# PLC.net
KiCad netlist of a schematic drawn in Altium Designer
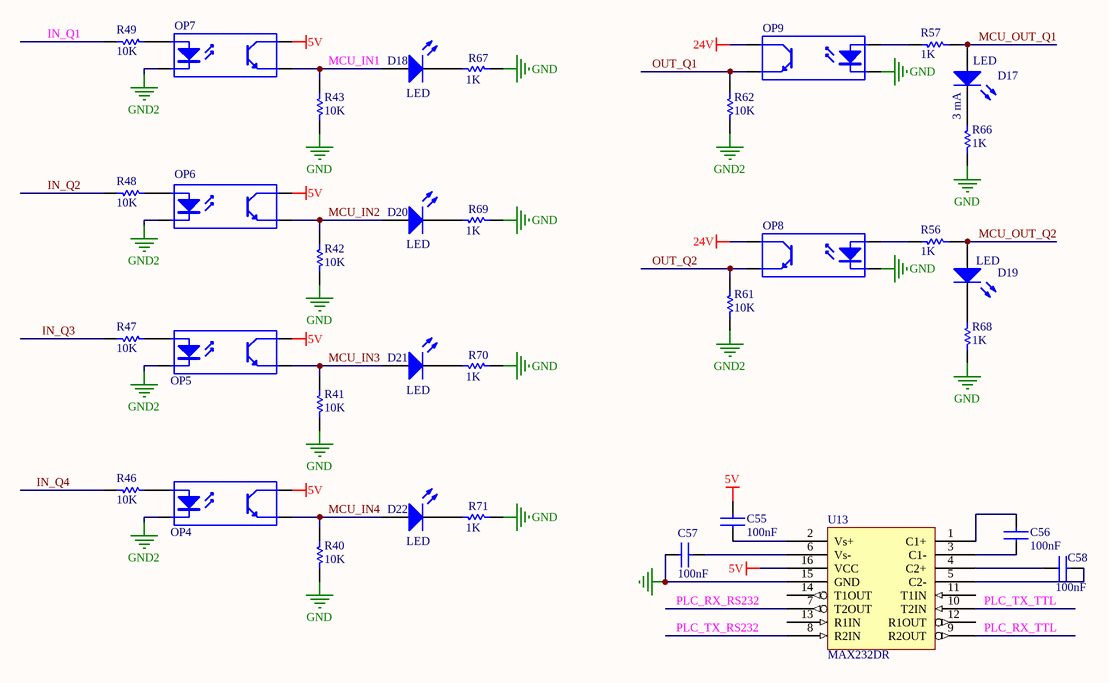
[diagram p0: PLC.SchDoc]

(export (version "E")
  (design (tool "Eeschema 10.0.6"))
  (components
    (comp (ref "C55") (value "100nF") (footprint "0805C") (libsource (lib "*") (part "CAP NP")))
    (comp (ref "C56") (value "100nF") (footprint "0805c") (libsource (lib "*") (part "CAP NP")))
    (comp (ref "C57") (value "100nF") (footprint "0805c") (libsource (lib "*") (part "CAP NP")))
    (comp (ref "C58") (value "100nF") (footprint "0805c") (libsource (lib "*") (part "CAP NP")))
    (comp (ref "D17")
      (value "LED")
      (footprint "0805D")
      (description "Typical BLUE SiC LED")
      (fields (field (name "PUBLISHER") "3 mA"))
      (libsource (lib "Miscellaneous Devices") (part "LED3"))
    )
    (comp (ref "D18")
      (value "LED")
      (footprint "0805D")
      (description "Typical BLUE SiC LED")
      (fields (field (name "PUBLISHER") "Altium Limited"))
      (libsource (lib "Miscellaneous Devices") (part "LED3"))
    )
    (comp (ref "D19")
      (value "LED")
      (footprint "0805D")
      (description "Typical BLUE SiC LED")
      (fields (field (name "PUBLISHER") "Altium Limited"))
      (libsource (lib "Miscellaneous Devices") (part "LED3"))
    )
    (comp (ref "D20")
      (value "LED")
      (footprint "0805D")
      (description "Typical BLUE SiC LED")
      (fields (field (name "PUBLISHER") "Altium Limited"))
      (libsource (lib "Miscellaneous Devices") (part "LED3"))
    )
    (comp (ref "D21")
      (value "LED")
      (footprint "0805D")
      (description "Typical BLUE SiC LED")
      (fields (field (name "PUBLISHER") "Altium Limited"))
      (libsource (lib "Miscellaneous Devices") (part "LED3"))
    )
    (comp (ref "D22")
      (value "LED")
      (footprint "0805D")
      (description "Typical BLUE SiC LED")
      (fields (field (name "PUBLISHER") "Altium Limited"))
      (libsource (lib "Miscellaneous Devices") (part "LED3"))
    )
    (comp (ref "OP4")
      (value "EL817")
      (footprint "EL817")
      (description "4-Pin Phototransistor Optocoupler")
      (fields (field (name "PUBLISHER") "Altium Limited"))
      (libsource (lib "Miscellaneous Devices") (part "Optoisolator1"))
    )
    (comp (ref "OP5")
      (value "EL817")
      (footprint "EL817")
      (description "4-Pin Phototransistor Optocoupler")
      (fields (field (name "PUBLISHER") "Altium Limited"))
      (libsource (lib "Miscellaneous Devices") (part "Optoisolator1"))
    )
    (comp (ref "OP6")
      (value "EL817")
      (footprint "EL817")
      (description "4-Pin Phototransistor Optocoupler")
      (fields (field (name "PUBLISHER") "Altium Limited"))
      (libsource (lib "Miscellaneous Devices") (part "Optoisolator1"))
    )
    (comp (ref "OP7")
      (value "EL817")
      (footprint "EL817")
      (description "4-Pin Phototransistor Optocoupler")
      (fields (field (name "PUBLISHER") "Altium Limited"))
      (libsource (lib "Miscellaneous Devices") (part "Optoisolator1"))
    )
    (comp (ref "OP8")
      (value "EL817")
      (footprint "EL817")
      (description "4-Pin Phototransistor Optocoupler")
      (libsource (lib "Miscellaneous Devices") (part "Optoisolator1"))
    )
    (comp (ref "OP9")
      (value "EL817")
      (footprint "EL817")
      (description "4-Pin Phototransistor Optocoupler")
      (fields (field (name "PUBLISHER") "Altium Limited"))
      (libsource (lib "Miscellaneous Devices") (part "Optoisolator1"))
    )
    (comp (ref "R40")
      (value "10K")
      (footprint "0805")
      (description "Semiconductor Resistor")
      (fields (field (name "PUBLISHER") "Altium Limited"))
      (libsource (lib "Miscellaneous Devices") (part "Res Semi"))
    )
    (comp (ref "R41")
      (value "10K")
      (footprint "0805")
      (description "Semiconductor Resistor")
      (fields (field (name "PUBLISHER") "Altium Limited"))
      (libsource (lib "Miscellaneous Devices") (part "Res Semi"))
    )
    (comp (ref "R42")
      (value "10K")
      (footprint "0805")
      (description "Semiconductor Resistor")
      (fields (field (name "PUBLISHER") "Altium Limited"))
      (libsource (lib "Miscellaneous Devices") (part "Res Semi"))
    )
    (comp (ref "R43")
      (value "10K")
      (footprint "0805")
      (description "Semiconductor Resistor")
      (fields (field (name "PUBLISHER") "Altium Limited"))
      (libsource (lib "Miscellaneous Devices") (part "Res Semi"))
    )
    (comp (ref "R46")
      (value "10K")
      (footprint "0805")
      (description "Semiconductor Resistor")
      (fields (field (name "PUBLISHER") "Altium Limited"))
      (libsource (lib "Miscellaneous Devices") (part "Res Semi"))
    )
    (comp (ref "R47")
      (value "10K")
      (footprint "0805")
      (description "Semiconductor Resistor")
      (fields (field (name "PUBLISHER") "Altium Limited"))
      (libsource (lib "Miscellaneous Devices") (part "Res Semi"))
    )
    (comp (ref "R48")
      (value "10K")
      (footprint "0805")
      (description "Semiconductor Resistor")
      (fields (field (name "PUBLISHER") "Altium Limited"))
      (libsource (lib "Miscellaneous Devices") (part "Res Semi"))
    )
    (comp (ref "R49")
      (value "10K")
      (footprint "0805")
      (description "Semiconductor Resistor")
      (fields (field (name "PUBLISHER") "Altium Limited"))
      (libsource (lib "Miscellaneous Devices") (part "Res Semi"))
    )
    (comp (ref "R56")
      (value "1K")
      (footprint "0805")
      (description "Semiconductor Resistor")
      (fields (field (name "PUBLISHER") "Altium Limited"))
      (libsource (lib "Miscellaneous Devices") (part "Res Semi"))
    )
    (comp (ref "R57")
      (value "1K")
      (footprint "0805")
      (description "Semiconductor Resistor")
      (fields (field (name "PUBLISHER") "Altium Limited"))
      (libsource (lib "Miscellaneous Devices") (part "Res Semi"))
    )
    (comp (ref "R61")
      (value "10K")
      (footprint "0805")
      (description "Semiconductor Resistor")
      (fields (field (name "PUBLISHER") "Altium Limited"))
      (libsource (lib "Miscellaneous Devices") (part "Res Semi"))
    )
    (comp (ref "R62")
      (value "10K")
      (footprint "0805")
      (description "Semiconductor Resistor")
      (fields (field (name "PUBLISHER") "Altium Limited"))
      (libsource (lib "Miscellaneous Devices") (part "Res Semi"))
    )
    (comp (ref "R66")
      (value "1K")
      (footprint "0805")
      (description "Semiconductor Resistor")
      (fields (field (name "PUBLISHER") "Altium Limited"))
      (libsource (lib "Miscellaneous Devices") (part "Res Semi"))
    )
    (comp (ref "R67")
      (value "1K")
      (footprint "0805")
      (description "Semiconductor Resistor")
      (fields (field (name "PUBLISHER") "Altium Limited"))
      (libsource (lib "Miscellaneous Devices") (part "Res Semi"))
    )
    (comp (ref "R68")
      (value "1K")
      (footprint "0805")
      (description "Semiconductor Resistor")
      (fields (field (name "PUBLISHER") "Altium Limited"))
      (libsource (lib "Miscellaneous Devices") (part "Res Semi"))
    )
    (comp (ref "R69")
      (value "1K")
      (footprint "0805")
      (description "Semiconductor Resistor")
      (fields (field (name "PUBLISHER") "Altium Limited"))
      (libsource (lib "Miscellaneous Devices") (part "Res Semi"))
    )
    (comp (ref "R70")
      (value "1K")
      (footprint "0805")
      (description "Semiconductor Resistor")
      (fields (field (name "PUBLISHER") "Altium Limited"))
      (libsource (lib "Miscellaneous Devices") (part "Res Semi"))
    )
    (comp (ref "R71")
      (value "1K")
      (footprint "0805")
      (description "Semiconductor Resistor")
      (fields (field (name "PUBLISHER") "Altium Limited"))
      (libsource (lib "Miscellaneous Devices") (part "Res Semi"))
    )
    (comp (ref "U13")
      (value "MAX232DR")
      (footprint "L16_N")
      (description "DUAL EIA-232 DRIVER/RECEIVER")
      (libsource (lib "*") (part "MAX232"))
    )
  )
  (nets
    (net (code "1") (name "/IN_Q1") (class "Default")
      (node (ref "R49") (pin "1") (pinfunction "1_1") (pintype "passive"))
    )
    (net (code "2") (name "/IN_Q2") (class "Default")
      (node (ref "R48") (pin "1") (pinfunction "1_1") (pintype "passive"))
    )
    (net (code "3") (name "/IN_Q3") (class "Default")
      (node (ref "R47") (pin "1") (pinfunction "1_1") (pintype "passive"))
    )
    (net (code "4") (name "/IN_Q4") (class "Default")
      (node (ref "R46") (pin "1") (pinfunction "1_1") (pintype "passive"))
    )
    (net (code "5") (name "/MCU_IN1") (class "Default")
      (node (ref "D18") (pin "1") (pinfunction "A_1") (pintype "passive"))
      (node (ref "OP7") (pin "3") (pinfunction "E_3") (pintype "passive"))
      (node (ref "R43") (pin "1") (pinfunction "1_1") (pintype "passive"))
    )
    (net (code "6") (name "/MCU_IN2") (class "Default")
      (node (ref "D20") (pin "1") (pinfunction "A_1") (pintype "passive"))
      (node (ref "OP6") (pin "3") (pinfunction "E_3") (pintype "passive"))
      (node (ref "R42") (pin "1") (pinfunction "1_1") (pintype "passive"))
    )
    (net (code "7") (name "/MCU_IN3") (class "Default")
      (node (ref "D21") (pin "1") (pinfunction "A_1") (pintype "passive"))
      (node (ref "OP5") (pin "3") (pinfunction "E_3") (pintype "passive"))
      (node (ref "R41") (pin "1") (pinfunction "1_1") (pintype "passive"))
    )
    (net (code "8") (name "/MCU_IN4") (class "Default")
      (node (ref "D22") (pin "1") (pinfunction "A_1") (pintype "passive"))
      (node (ref "OP4") (pin "3") (pinfunction "E_3") (pintype "passive"))
      (node (ref "R40") (pin "1") (pinfunction "1_1") (pintype "passive"))
    )
    (net (code "9") (name "/MCU_OUT_Q1") (class "Default")
      (node (ref "D17") (pin "1") (pinfunction "A_1") (pintype "passive"))
      (node (ref "R57") (pin "2") (pinfunction "2_2") (pintype "passive"))
    )
    (net (code "10") (name "/MCU_OUT_Q2") (class "Default")
      (node (ref "D19") (pin "1") (pinfunction "A_1") (pintype "passive"))
      (node (ref "R56") (pin "2") (pinfunction "2_2") (pintype "passive"))
    )
    (net (code "11") (name "/OUT_Q1") (class "Default")
      (node (ref "OP9") (pin "3") (pinfunction "E_3") (pintype "passive"))
      (node (ref "R62") (pin "2") (pinfunction "2_2") (pintype "passive"))
    )
    (net (code "12") (name "/OUT_Q2") (class "Default")
      (node (ref "OP8") (pin "3") (pinfunction "E_3") (pintype "passive"))
      (node (ref "R61") (pin "2") (pinfunction "2_2") (pintype "passive"))
    )
    (net (code "13") (name "/PLC_RX_RS232") (class "Default")
      (node (ref "U13") (pin "7") (pinfunction "T2OUT_7") (pintype "output"))
    )
    (net (code "14") (name "/PLC_RX_TTL") (class "Default")
      (node (ref "U13") (pin "9") (pinfunction "R2OUT_9") (pintype "output"))
    )
    (net (code "15") (name "/PLC_TX_RS232") (class "Default")
      (node (ref "U13") (pin "8") (pinfunction "R2IN_8") (pintype "input"))
    )
    (net (code "16") (name "/PLC_TX_TTL") (class "Default")
      (node (ref "U13") (pin "10") (pinfunction "T2IN_10") (pintype "input"))
    )
    (net (code "17") (name "5V") (class "Default")
      (node (ref "C55") (pin "2") (pinfunction "2_2") (pintype "passive"))
      (node (ref "OP4") (pin "4") (pinfunction "C_4") (pintype "passive"))
      (node (ref "OP5") (pin "4") (pinfunction "C_4") (pintype "passive"))
      (node (ref "OP6") (pin "4") (pinfunction "C_4") (pintype "passive"))
      (node (ref "OP7") (pin "4") (pinfunction "C_4") (pintype "passive"))
      (node (ref "U13") (pin "16") (pinfunction "VCC_16") (pintype "power_in"))
    )
    (net (code "18") (name "24V") (class "Default")
      (node (ref "OP8") (pin "4") (pinfunction "C_4") (pintype "passive"))
      (node (ref "OP9") (pin "4") (pinfunction "C_4") (pintype "passive"))
    )
    (net (code "19") (name "GND") (class "Default")
      (node (ref "C57") (pin "1") (pinfunction "1_1") (pintype "passive"))
      (node (ref "OP8") (pin "2") (pinfunction "K_2") (pintype "passive"))
      (node (ref "OP9") (pin "2") (pinfunction "K_2") (pintype "passive"))
      (node (ref "R40") (pin "2") (pinfunction "2_2") (pintype "passive"))
      (node (ref "R41") (pin "2") (pinfunction "2_2") (pintype "passive"))
      (node (ref "R42") (pin "2") (pinfunction "2_2") (pintype "passive"))
      (node (ref "R43") (pin "2") (pinfunction "2_2") (pintype "passive"))
      (node (ref "R66") (pin "2") (pinfunction "2_2") (pintype "passive"))
      (node (ref "R67") (pin "2") (pinfunction "2_2") (pintype "passive"))
      (node (ref "R68") (pin "2") (pinfunction "2_2") (pintype "passive"))
      (node (ref "R69") (pin "2") (pinfunction "2_2") (pintype "passive"))
      (node (ref "R70") (pin "2") (pinfunction "2_2") (pintype "passive"))
      (node (ref "R71") (pin "2") (pinfunction "2_2") (pintype "passive"))
      (node (ref "U13") (pin "15") (pinfunction "GND_15") (pintype "power_in"))
    )
    (net (code "20") (name "GND2") (class "Default")
      (node (ref "OP4") (pin "2") (pinfunction "K_2") (pintype "passive"))
      (node (ref "OP5") (pin "2") (pinfunction "K_2") (pintype "passive"))
      (node (ref "OP6") (pin "2") (pinfunction "K_2") (pintype "passive"))
      (node (ref "OP7") (pin "2") (pinfunction "K_2") (pintype "passive"))
      (node (ref "R61") (pin "1") (pinfunction "1_1") (pintype "passive"))
      (node (ref "R62") (pin "1") (pinfunction "1_1") (pintype "passive"))
    )
    (net (code "21") (name "Net-(D17-K)") (class "Default")
      (node (ref "D17") (pin "2") (pinfunction "K_2") (pintype "passive"))
      (node (ref "R66") (pin "1") (pinfunction "1_1") (pintype "passive"))
    )
    (net (code "22") (name "Net-(D18-K)") (class "Default")
      (node (ref "D18") (pin "2") (pinfunction "K_2") (pintype "passive"))
      (node (ref "R67") (pin "1") (pinfunction "1_1") (pintype "passive"))
    )
    (net (code "23") (name "Net-(D19-K)") (class "Default")
      (node (ref "D19") (pin "2") (pinfunction "K_2") (pintype "passive"))
      (node (ref "R68") (pin "1") (pinfunction "1_1") (pintype "passive"))
    )
    (net (code "24") (name "Net-(D20-K)") (class "Default")
      (node (ref "D20") (pin "2") (pinfunction "K_2") (pintype "passive"))
      (node (ref "R69") (pin "1") (pinfunction "1_1") (pintype "passive"))
    )
    (net (code "25") (name "Net-(D21-K)") (class "Default")
      (node (ref "D21") (pin "2") (pinfunction "K_2") (pintype "passive"))
      (node (ref "R70") (pin "1") (pinfunction "1_1") (pintype "passive"))
    )
    (net (code "26") (name "Net-(D22-K)") (class "Default")
      (node (ref "D22") (pin "2") (pinfunction "K_2") (pintype "passive"))
      (node (ref "R71") (pin "1") (pinfunction "1_1") (pintype "passive"))
    )
    (net (code "27") (name "Net-(OP4-A)") (class "Default")
      (node (ref "OP4") (pin "1") (pinfunction "A_1") (pintype "passive"))
      (node (ref "R46") (pin "2") (pinfunction "2_2") (pintype "passive"))
    )
    (net (code "28") (name "Net-(OP5-A)") (class "Default")
      (node (ref "OP5") (pin "1") (pinfunction "A_1") (pintype "passive"))
      (node (ref "R47") (pin "2") (pinfunction "2_2") (pintype "passive"))
    )
    (net (code "29") (name "Net-(OP6-A)") (class "Default")
      (node (ref "OP6") (pin "1") (pinfunction "A_1") (pintype "passive"))
      (node (ref "R48") (pin "2") (pinfunction "2_2") (pintype "passive"))
    )
    (net (code "30") (name "Net-(OP7-A)") (class "Default")
      (node (ref "OP7") (pin "1") (pinfunction "A_1") (pintype "passive"))
      (node (ref "R49") (pin "2") (pinfunction "2_2") (pintype "passive"))
    )
    (net (code "31") (name "Net-(OP8-A)") (class "Default")
      (node (ref "OP8") (pin "1") (pinfunction "A_1") (pintype "passive"))
      (node (ref "R56") (pin "1") (pinfunction "1_1") (pintype "passive"))
    )
    (net (code "32") (name "Net-(OP9-A)") (class "Default")
      (node (ref "OP9") (pin "1") (pinfunction "A_1") (pintype "passive"))
      (node (ref "R57") (pin "1") (pinfunction "1_1") (pintype "passive"))
    )
    (net (code "33") (name "Net-(U13-C1+)") (class "Default")
      (node (ref "C56") (pin "2") (pinfunction "2_2") (pintype "passive"))
      (node (ref "U13") (pin "1") (pinfunction "C1+_1") (pintype "passive"))
    )
    (net (code "34") (name "Net-(U13-C1-)") (class "Default")
      (node (ref "C56") (pin "1") (pinfunction "1_1") (pintype "passive"))
      (node (ref "U13") (pin "3") (pinfunction "C1-_3") (pintype "passive"))
    )
    (net (code "35") (name "Net-(U13-C2+)") (class "Default")
      (node (ref "C58") (pin "1") (pinfunction "1_1") (pintype "passive"))
      (node (ref "U13") (pin "4") (pinfunction "C2+_4") (pintype "passive"))
    )
    (net (code "36") (name "Net-(U13-C2-)") (class "Default")
      (node (ref "C58") (pin "2") (pinfunction "2_2") (pintype "passive"))
      (node (ref "U13") (pin "5") (pinfunction "C2-_5") (pintype "passive"))
    )
    (net (code "37") (name "Net-(U13-Vs+)") (class "Default")
      (node (ref "C55") (pin "1") (pinfunction "1_1") (pintype "passive"))
      (node (ref "U13") (pin "2") (pinfunction "Vs+_2") (pintype "passive"))
    )
    (net (code "38") (name "Net-(U13-Vs-)") (class "Default")
      (node (ref "C57") (pin "2") (pinfunction "2_2") (pintype "passive"))
      (node (ref "U13") (pin "6") (pinfunction "Vs-_6") (pintype "passive"))
    )
    (net (code "39") (name "unconnected-(U13-R1IN-Pad13)") (class "Default")
      (node (ref "U13") (pin "13") (pinfunction "R1IN_13") (pintype "input"))
    )
    (net (code "40") (name "unconnected-(U13-R1OUT-Pad12)") (class "Default")
      (node (ref "U13") (pin "12") (pinfunction "R1OUT_12") (pintype "output"))
    )
    (net (code "41") (name "unconnected-(U13-T1IN-Pad11)") (class "Default")
      (node (ref "U13") (pin "11") (pinfunction "T1IN_11") (pintype "input"))
    )
    (net (code "42") (name "unconnected-(U13-T1OUT-Pad14)") (class "Default")
      (node (ref "U13") (pin "14") (pinfunction "T1OUT_14") (pintype "output"))
    )
  )
)
